# piezo-preamp-tickler_V2-RevC.net
KiCad netlist of a schematic drawn in EAGLE
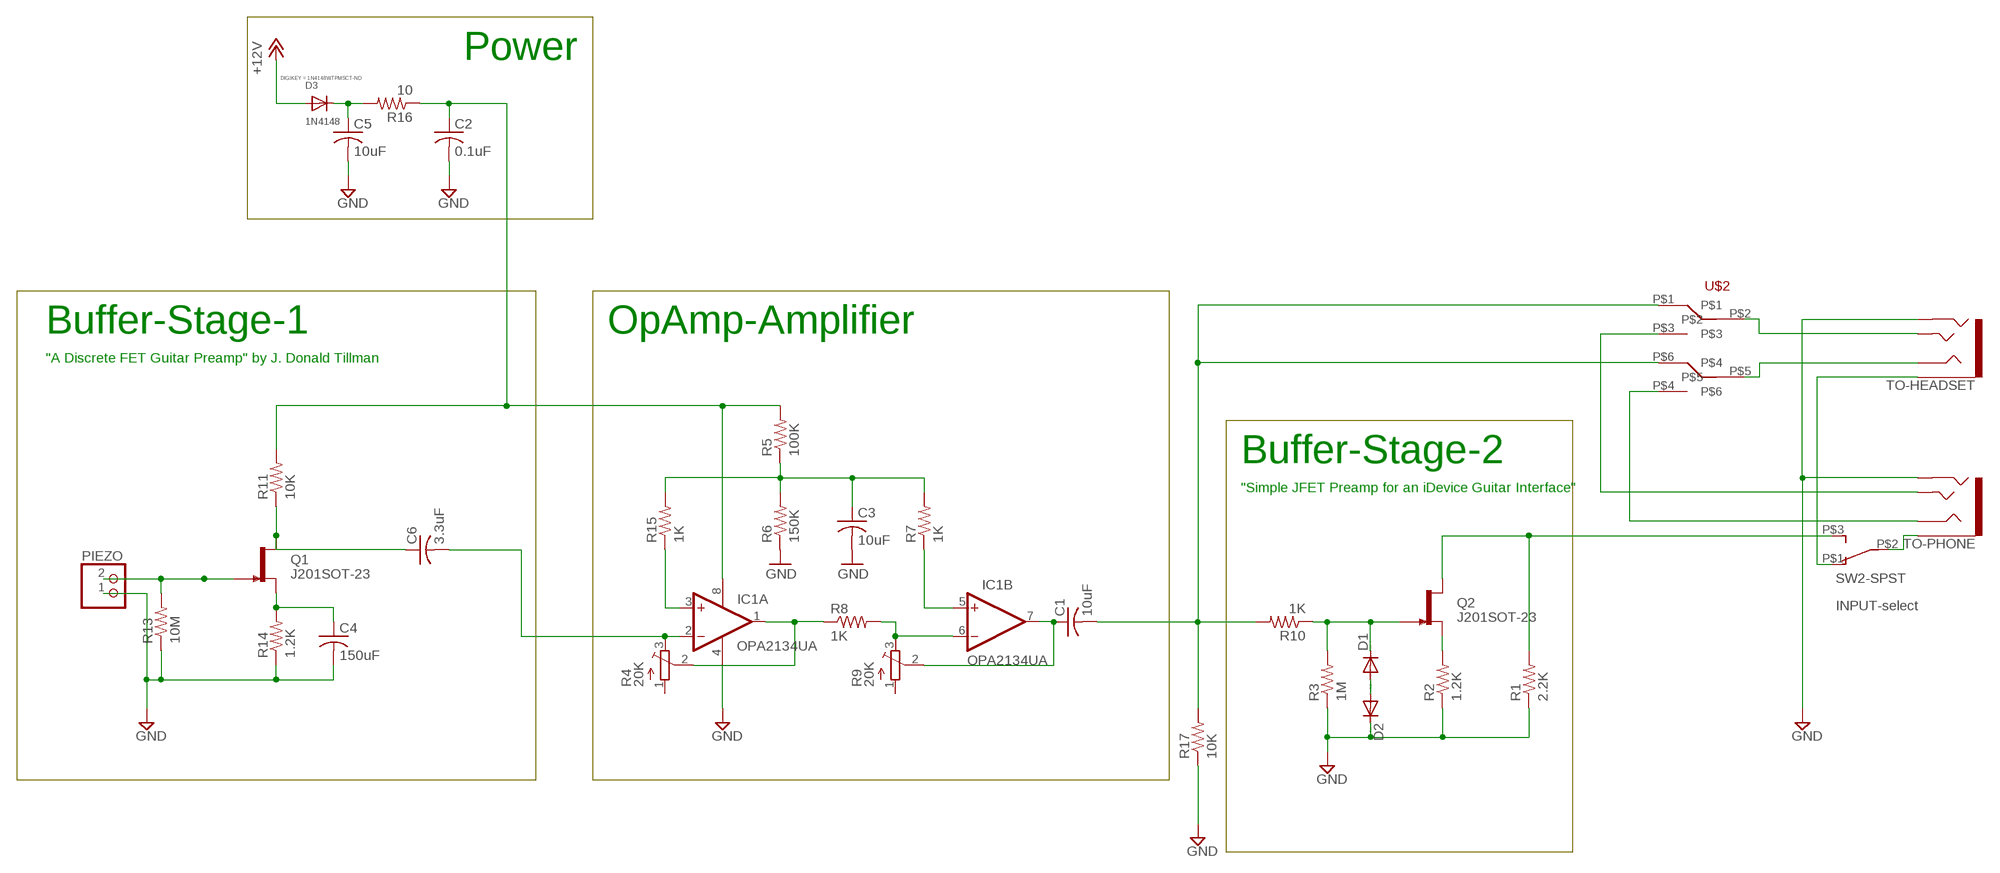
[diagram p0: schematic, sheet 1]
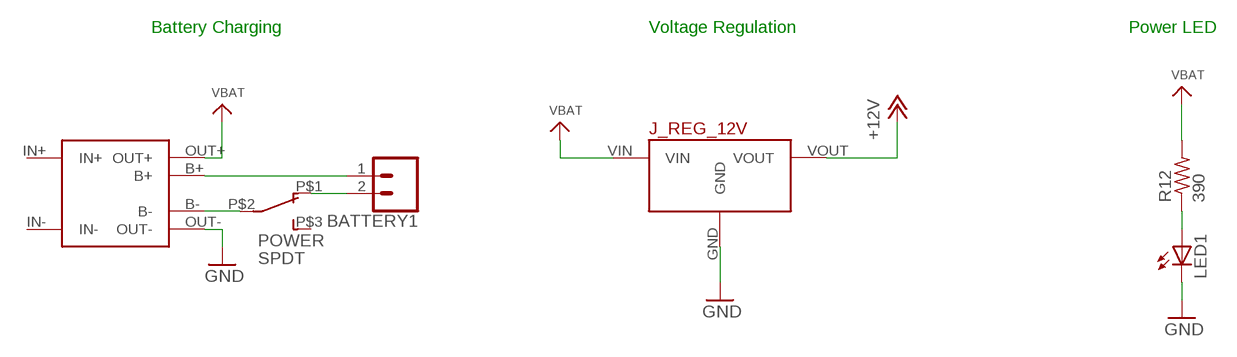
[diagram p1: schematic, sheet 2]

(export (version "E")
  (design (tool "Eeschema 10.0.6"))
  (components
    (comp (ref "C1")
      (value "10uF")
      (footprint "eagle-import:C0805K")
      (libsource (lib "eagle-import") (part "C-USC0805K"))
    )
    (comp (ref "C2")
      (value "0.1uF")
      (footprint "eagle-import:C0805K")
      (libsource (lib "eagle-import") (part "C-USC0805K"))
    )
    (comp (ref "C3")
      (value "10uF")
      (footprint "eagle-import:C0805K")
      (libsource (lib "eagle-import") (part "C-USC0805K"))
    )
    (comp (ref "C4")
      (value "150uF")
      (footprint "eagle-import:C3216")
      (libsource (lib "eagle-import") (part "C-USC3216"))
    )
    (comp (ref "C5")
      (value "10uF")
      (footprint "eagle-import:C0805K")
      (libsource (lib "eagle-import") (part "C-USC0805K"))
    )
    (comp (ref "C6")
      (value "3.3uF")
      (footprint "eagle-import:C0805K")
      (libsource (lib "eagle-import") (part "C-USC0805K"))
    )
    (comp (ref "D1")
      (value "DIODE-SOD123")
      (footprint "eagle-import:SOD123")
      (libsource (lib "eagle-import") (part "DIODE-SOD123"))
    )
    (comp (ref "D2")
      (value "DIODE-SOD123")
      (footprint "eagle-import:SOD123")
      (libsource (lib "eagle-import") (part "DIODE-SOD123"))
    )
    (comp (ref "D3")
      (value "1N4148")
      (footprint "eagle-import:SOD-123")
      (fields (field (name "DIGIKEY") "1N4148WTPMSCT-ND"))
      (libsource (lib "eagle-import") (part "DIODESOD-123"))
    )
    (comp (ref "IC1")
      (value "OPA2134UA")
      (footprint "eagle-import:SO08")
      (libsource (lib "eagle-import") (part "OPA2UA134"))
    )
    (comp (ref "PIEZO")
      (value "JST_2PIN-THM")
      (footprint "eagle-import:JST-PH-2-THM")
      (libsource (lib "eagle-import") (part "JST_2PIN-THM"))
    )
    (comp (ref "Q1")
      (value "J201SOT-23")
      (footprint "eagle-import:SOT23-3")
      (libsource (lib "eagle-import") (part "J201SOT-23"))
    )
    (comp (ref "Q2")
      (value "J201SOT-23")
      (footprint "eagle-import:SOT23-3")
      (libsource (lib "eagle-import") (part "J201SOT-23"))
    )
    (comp (ref "R1")
      (value "2.2K")
      (footprint "eagle-import:R0603")
      (libsource (lib "eagle-import") (part "R-US_R0603"))
    )
    (comp (ref "R2")
      (value "1.2K")
      (footprint "eagle-import:R0603")
      (libsource (lib "eagle-import") (part "R-US_R0603"))
    )
    (comp (ref "R3")
      (value "1M")
      (footprint "eagle-import:R0603")
      (libsource (lib "eagle-import") (part "R-US_R0603"))
    )
    (comp (ref "R4")
      (value "20K")
      (footprint "eagle-import:TC33X")
      (libsource (lib "eagle-import") (part "TRIMPOTTC33X"))
    )
    (comp (ref "R5")
      (value "100K")
      (footprint "eagle-import:R0603")
      (libsource (lib "eagle-import") (part "R-US_R0603"))
    )
    (comp (ref "R6")
      (value "150K")
      (footprint "eagle-import:R0603")
      (libsource (lib "eagle-import") (part "R-US_R0603"))
    )
    (comp (ref "R7")
      (value "1K")
      (footprint "eagle-import:R0603")
      (libsource (lib "eagle-import") (part "R-US_R0603"))
    )
    (comp (ref "R8")
      (value "1K")
      (footprint "eagle-import:R0603")
      (libsource (lib "eagle-import") (part "R-US_R0603"))
    )
    (comp (ref "R9")
      (value "20K")
      (footprint "eagle-import:TC33X")
      (libsource (lib "eagle-import") (part "TRIMPOTTC33X"))
    )
    (comp (ref "R10")
      (value "1K")
      (footprint "eagle-import:R0603")
      (libsource (lib "eagle-import") (part "R-US_R0603"))
    )
    (comp (ref "R11")
      (value "10K")
      (footprint "eagle-import:R0603")
      (libsource (lib "eagle-import") (part "R-US_R0603"))
    )
    (comp (ref "R13")
      (value "10M")
      (footprint "eagle-import:R0603")
      (libsource (lib "eagle-import") (part "R-US_R0603"))
    )
    (comp (ref "R14")
      (value "1.2K")
      (footprint "eagle-import:R0603")
      (libsource (lib "eagle-import") (part "R-US_R0603"))
    )
    (comp (ref "R15")
      (value "1K")
      (footprint "eagle-import:R0603")
      (libsource (lib "eagle-import") (part "R-US_R0603"))
    )
    (comp (ref "R16")
      (value "10")
      (footprint "eagle-import:R0603")
      (libsource (lib "eagle-import") (part "R-US_R0603"))
    )
    (comp (ref "R17")
      (value "10K")
      (footprint "eagle-import:R0603")
      (libsource (lib "eagle-import") (part "R-US_R0603"))
    )
    (comp (ref "SW2-SPST")
      (value "INPUT-select")
      (footprint "eagle-import:SWITCH_SPDT_CL-SB-12B")
      (libsource (lib "eagle-import") (part "SWITCH_SPDTCL-SB-12B"))
    )
    (comp (ref "TO-HEADSET")
      (value "AUDIO-JACK3LGPADS")
      (footprint "eagle-import:AUDIO-JACK-TRRS-SMD")
      (libsource (lib "eagle-import") (part "AUDIO-JACK3LGPADS"))
    )
    (comp (ref "TO-PHONE")
      (value "AUDIO-JACK3LGPADS")
      (footprint "eagle-import:AUDIO-JACK-TRRS-SMD")
      (libsource (lib "eagle-import") (part "AUDIO-JACK3LGPADS"))
    )
    (comp (ref "U$2")
      (value "SWITCH_DPDT")
      (footprint "eagle-import:SWITCH_DPDT_CL-SB-12B")
      (libsource (lib "eagle-import") (part "SWITCH_DPDT"))
    )
    (comp (ref "BATTERY1")
      (value "CONN_02LOCK")
      (footprint "eagle-import:1X02_LOCK")
      (libsource (lib "eagle-import") (part "CONN_02LOCK"))
    )
    (comp (ref "J_REG_12V")
      (value "POLOLU_VOLTAGE_REGULATORS_3PIN")
      (footprint "eagle-import:POLOLU_5V-12V_STEPUP_U3V12F5-U3V12F12")
      (libsource (lib "eagle-import") (part "POLOLU_VOLTAGE_REGULATORS_3PIN"))
    )
    (comp (ref "LED1")
      (value "LED3MM")
      (footprint "eagle-import:LED3MM")
      (libsource (lib "eagle-import") (part "LED3MM"))
    )
    (comp (ref "POWER")
      (value "SPDT")
      (footprint "eagle-import:SWITCH_SPDT_CL-SB-12B")
      (libsource (lib "eagle-import") (part "SWITCH_SPDTCL-SB-12B"))
    )
    (comp (ref "R12")
      (value "390")
      (footprint "eagle-import:R0805")
      (libsource (lib "eagle-import") (part "R-US_R0805"))
    )
    (comp (ref "USB-LIPO-CHARGER")
      (value "TP4056-MODULE")
      (footprint "eagle-import:TP4056-LITHIUM-PROTECTED-MODULE")
      (libsource (lib "eagle-import") (part "TP4056-MODULE"))
    )
  )
  (nets
    (net (code "1") (name "+12V") (class "Default")
      (node (ref "D3") (pin "A") (pinfunction "A_A") (pintype "passive"))
      (node (ref "J_REG_12V") (pin "VOUT") (pinfunction "VOUT_VOUT") (pintype "bidirectional"))
    )
    (net (code "2") (name "GND") (class "Default")
      (node (ref "C2") (pin "2") (pinfunction "2_2") (pintype "passive"))
      (node (ref "C3") (pin "2") (pinfunction "2_2") (pintype "passive"))
      (node (ref "C4") (pin "2") (pinfunction "2_2") (pintype "passive"))
      (node (ref "C5") (pin "2") (pinfunction "2_2") (pintype "passive"))
      (node (ref "D2") (pin "C") (pinfunction "C_C") (pintype "passive"))
      (node (ref "IC1") (pin "4") (pinfunction "V-_4") (pintype "power_in"))
      (node (ref "J_REG_12V") (pin "GND") (pinfunction "GND_GND") (pintype "bidirectional"))
      (node (ref "LED1") (pin "K") (pinfunction "C_K") (pintype "passive"))
      (node (ref "PIEZO") (pin "1") (pinfunction "2_1") (pintype "passive"))
      (node (ref "R1") (pin "1") (pinfunction "1_1") (pintype "passive"))
      (node (ref "R13") (pin "1") (pinfunction "1_1") (pintype "passive"))
      (node (ref "R14") (pin "1") (pinfunction "1_1") (pintype "passive"))
      (node (ref "R17") (pin "1") (pinfunction "1_1") (pintype "passive"))
      (node (ref "R2") (pin "1") (pinfunction "1_1") (pintype "passive"))
      (node (ref "R3") (pin "1") (pinfunction "1_1") (pintype "passive"))
      (node (ref "R6") (pin "1") (pinfunction "1_1") (pintype "passive"))
      (node (ref "TO-HEADSET") (pin "RING2") (pinfunction "RING2_RING2") (pintype "bidirectional"))
      (node (ref "TO-PHONE") (pin "RING2") (pinfunction "RING2_RING2") (pintype "bidirectional"))
      (node (ref "USB-LIPO-CHARGER") (pin "OUT-") (pinfunction "OUT-_OUT-") (pintype "power_in"))
    )
    (net (code "3") (name "IN+") (class "Default")
      (node (ref "USB-LIPO-CHARGER") (pin "IN+") (pinfunction "IN+_IN+") (pintype "power_in"))
    )
    (net (code "4") (name "IN-") (class "Default")
      (node (ref "USB-LIPO-CHARGER") (pin "IN-") (pinfunction "IN-_IN-") (pintype "power_in"))
    )
    (net (code "5") (name "Net-(BATTERY1-Pad1)") (class "Default")
      (node (ref "BATTERY1") (pin "1") (pinfunction "1_1") (pintype "passive"))
      (node (ref "USB-LIPO-CHARGER") (pin "B+") (pinfunction "B+_B+") (pintype "power_in"))
    )
    (net (code "6") (name "Net-(C3-Pad1)") (class "Default")
      (node (ref "C3") (pin "1") (pinfunction "1_1") (pintype "passive"))
      (node (ref "R15") (pin "2") (pinfunction "2_2") (pintype "passive"))
      (node (ref "R5") (pin "1") (pinfunction "1_1") (pintype "passive"))
      (node (ref "R6") (pin "2") (pinfunction "2_2") (pintype "passive"))
      (node (ref "R7") (pin "2") (pinfunction "2_2") (pintype "passive"))
    )
    (net (code "7") (name "Net-(C5-Pad1)") (class "Default")
      (node (ref "C5") (pin "1") (pinfunction "1_1") (pintype "passive"))
      (node (ref "D3") (pin "C") (pinfunction "C_C") (pintype "passive"))
      (node (ref "R16") (pin "2") (pinfunction "2_2") (pintype "passive"))
    )
    (net (code "8") (name "Net-(D1-PadA)") (class "Default")
      (node (ref "D1") (pin "A") (pinfunction "A_A") (pintype "passive"))
      (node (ref "D2") (pin "A") (pinfunction "A_A") (pintype "passive"))
    )
    (net (code "9") (name "Net-(IC1A-+IN)") (class "Default")
      (node (ref "IC1") (pin "3") (pinfunction "+IN_3") (pintype "input"))
      (node (ref "R15") (pin "1") (pinfunction "1_1") (pintype "passive"))
    )
    (net (code "10") (name "Net-(IC1A--IN)") (class "Default")
      (node (ref "C6") (pin "2") (pinfunction "2_2") (pintype "passive"))
      (node (ref "IC1") (pin "2") (pinfunction "-IN_2") (pintype "input"))
      (node (ref "R4") (pin "3") (pinfunction "E_3") (pintype "passive"))
    )
    (net (code "11") (name "Net-(IC1A-OUT)") (class "Default")
      (node (ref "IC1") (pin "1") (pinfunction "OUT_1") (pintype "output"))
      (node (ref "R4") (pin "2") (pinfunction "S_2") (pintype "passive"))
      (node (ref "R8") (pin "1") (pinfunction "1_1") (pintype "passive"))
    )
    (net (code "12") (name "Net-(IC1A-V+)") (class "Default")
      (node (ref "C2") (pin "1") (pinfunction "1_1") (pintype "passive"))
      (node (ref "IC1") (pin "8") (pinfunction "V+_8") (pintype "power_in"))
      (node (ref "R11") (pin "2") (pinfunction "2_2") (pintype "passive"))
      (node (ref "R16") (pin "1") (pinfunction "1_1") (pintype "passive"))
      (node (ref "R5") (pin "2") (pinfunction "2_2") (pintype "passive"))
    )
    (net (code "13") (name "Net-(IC1B-+IN)") (class "Default")
      (node (ref "IC1") (pin "5") (pinfunction "+IN_5") (pintype "input"))
      (node (ref "R7") (pin "1") (pinfunction "1_1") (pintype "passive"))
    )
    (net (code "14") (name "Net-(IC1B--IN)") (class "Default")
      (node (ref "IC1") (pin "6") (pinfunction "-IN_6") (pintype "input"))
      (node (ref "R8") (pin "2") (pinfunction "2_2") (pintype "passive"))
      (node (ref "R9") (pin "3") (pinfunction "E_3") (pintype "passive"))
    )
    (net (code "15") (name "Net-(IC1B-OUT)") (class "Default")
      (node (ref "C1") (pin "1") (pinfunction "1_1") (pintype "passive"))
      (node (ref "IC1") (pin "7") (pinfunction "OUT_7") (pintype "output"))
      (node (ref "R9") (pin "2") (pinfunction "S_2") (pintype "passive"))
    )
    (net (code "16") (name "Net-(LED1-PadA)") (class "Default")
      (node (ref "LED1") (pin "A") (pinfunction "A_A") (pintype "passive"))
      (node (ref "R12") (pin "1") (pinfunction "1_1") (pintype "passive"))
    )
    (net (code "17") (name "Net-(PIEZO-1)") (class "Default")
      (node (ref "PIEZO") (pin "2") (pinfunction "1_2") (pintype "passive"))
      (node (ref "Q1") (pin "3") (pinfunction "G_3") (pintype "passive"))
      (node (ref "R13") (pin "2") (pinfunction "2_2") (pintype "passive"))
    )
    (net (code "18") (name "Net-(POWER-1)") (class "Default")
      (node (ref "BATTERY1") (pin "2") (pinfunction "2_2") (pintype "passive"))
      (node (ref "POWER") (pin "P$1") (pinfunction "1_P$1") (pintype "passive"))
    )
    (net (code "19") (name "Net-(POWER-2)") (class "Default")
      (node (ref "POWER") (pin "P$2") (pinfunction "2_P$2") (pintype "passive"))
      (node (ref "USB-LIPO-CHARGER") (pin "B-") (pinfunction "B-_B-") (pintype "power_in"))
    )
    (net (code "20") (name "Net-(Q1-D)") (class "Default")
      (node (ref "C6") (pin "1") (pinfunction "1_1") (pintype "passive"))
      (node (ref "Q1") (pin "1") (pinfunction "D_1") (pintype "passive"))
      (node (ref "R11") (pin "1") (pinfunction "1_1") (pintype "passive"))
    )
    (net (code "21") (name "Net-(Q1-S)") (class "Default")
      (node (ref "C4") (pin "1") (pinfunction "1_1") (pintype "passive"))
      (node (ref "Q1") (pin "2") (pinfunction "S_2") (pintype "passive"))
      (node (ref "R14") (pin "2") (pinfunction "2_2") (pintype "passive"))
    )
    (net (code "22") (name "Net-(Q2-D)") (class "Default")
      (node (ref "Q2") (pin "1") (pinfunction "D_1") (pintype "passive"))
      (node (ref "R1") (pin "2") (pinfunction "2_2") (pintype "passive"))
      (node (ref "SW2-SPST") (pin "P$3") (pinfunction "3_P$3") (pintype "passive"))
    )
    (net (code "23") (name "Net-(Q2-G)") (class "Default")
      (node (ref "D1") (pin "C") (pinfunction "C_C") (pintype "passive"))
      (node (ref "Q2") (pin "3") (pinfunction "G_3") (pintype "passive"))
      (node (ref "R10") (pin "1") (pinfunction "1_1") (pintype "passive"))
      (node (ref "R3") (pin "2") (pinfunction "2_2") (pintype "passive"))
    )
    (net (code "24") (name "Net-(Q2-S)") (class "Default")
      (node (ref "Q2") (pin "2") (pinfunction "S_2") (pintype "passive"))
      (node (ref "R2") (pin "2") (pinfunction "2_2") (pintype "passive"))
    )
    (net (code "25") (name "Net-(SW2-SPST-1)") (class "Default")
      (node (ref "SW2-SPST") (pin "P$1") (pinfunction "1_P$1") (pintype "passive"))
      (node (ref "TO-HEADSET") (pin "EARTH") (pinfunction "EARTH_EARTH") (pintype "bidirectional"))
    )
    (net (code "26") (name "Net-(SW2-SPST-2)") (class "Default")
      (node (ref "SW2-SPST") (pin "P$2") (pinfunction "2_P$2") (pintype "passive"))
      (node (ref "TO-PHONE") (pin "EARTH") (pinfunction "EARTH_EARTH") (pintype "bidirectional"))
    )
    (net (code "27") (name "Net-(TO-HEADSET-PadRING1)") (class "Default")
      (node (ref "TO-HEADSET") (pin "RING1") (pinfunction "RING1_RING1") (pintype "bidirectional"))
      (node (ref "U$2") (pin "P$5") (pinfunction "P$5_P$5") (pintype "bidirectional"))
    )
    (net (code "28") (name "Net-(TO-HEADSET-PadTIP)") (class "Default")
      (node (ref "TO-HEADSET") (pin "TIP") (pinfunction "TIP_TIP") (pintype "bidirectional"))
      (node (ref "U$2") (pin "P$2") (pinfunction "P$2_P$2") (pintype "bidirectional"))
    )
    (net (code "29") (name "Net-(TO-PHONE-PadTIP)") (class "Default")
      (node (ref "TO-PHONE") (pin "TIP") (pinfunction "TIP_TIP") (pintype "bidirectional"))
      (node (ref "U$2") (pin "P$3") (pinfunction "P$3_P$3") (pintype "bidirectional"))
    )
    (net (code "30") (name "Net-(U$2-P$4)") (class "Default")
      (node (ref "C1") (pin "2") (pinfunction "2_2") (pintype "passive"))
      (node (ref "R10") (pin "2") (pinfunction "2_2") (pintype "passive"))
      (node (ref "R17") (pin "2") (pinfunction "2_2") (pintype "passive"))
      (node (ref "U$2") (pin "P$1") (pinfunction "P$1_P$1") (pintype "bidirectional"))
      (node (ref "U$2") (pin "P$6") (pinfunction "P$4_P$6") (pintype "bidirectional"))
    )
    (net (code "31") (name "Net-(U$2-P$6)") (class "Default")
      (node (ref "TO-PHONE") (pin "RING1") (pinfunction "RING1_RING1") (pintype "bidirectional"))
      (node (ref "U$2") (pin "P$4") (pinfunction "P$6_P$4") (pintype "bidirectional"))
    )
    (net (code "32") (name "VBAT") (class "Default")
      (node (ref "J_REG_12V") (pin "VIN") (pinfunction "VIN_VIN") (pintype "bidirectional"))
      (node (ref "R12") (pin "2") (pinfunction "2_2") (pintype "passive"))
      (node (ref "USB-LIPO-CHARGER") (pin "OUT+") (pinfunction "OUT+_OUT+") (pintype "power_in"))
    )
    (net (code "33") (name "unconnected-(POWER-3-PadP$3)") (class "Default")
      (node (ref "POWER") (pin "P$3") (pinfunction "3_P$3") (pintype "passive"))
    )
    (net (code "34") (name "unconnected-(R4-A-Pad1)") (class "Default")
      (node (ref "R4") (pin "1") (pinfunction "A_1") (pintype "passive"))
    )
    (net (code "35") (name "unconnected-(R9-A-Pad1)") (class "Default")
      (node (ref "R9") (pin "1") (pinfunction "A_1") (pintype "passive"))
    )
  )
)
